# MCU.net
KiCad netlist of a schematic drawn in Altium Designer
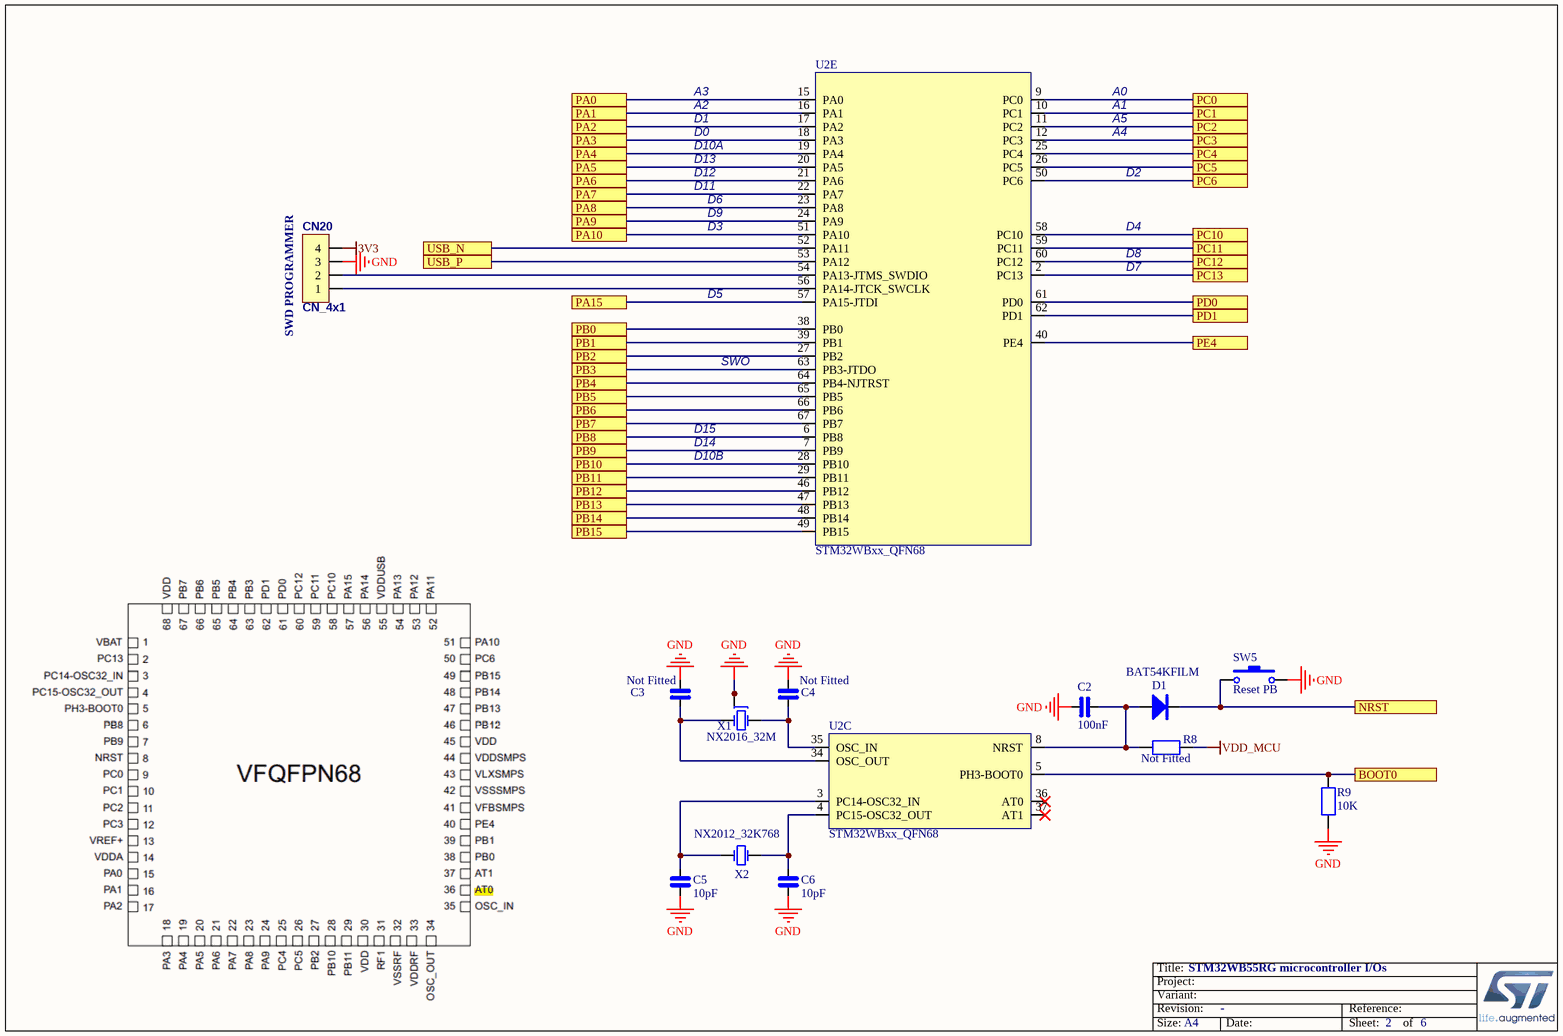
[diagram p0: MCU.SchDoc]

(export (version "E")
  (design (tool "Eeschema 10.0.6"))
  (components
    (comp (ref "C2")
      (value "100nF")
      (footprint "0603_CAP_NPOL")
      (description "Capacitor_not polarized")
      (libsource (lib "ST_Lib3D") (part "CAP_NPOL"))
    )
    (comp (ref "C3")
      (value "TBD")
      (footprint "0603_CAP_NPOL")
      (description "Capacitor_not polarized")
      (fields (field (name "FITTED") "Not Fitted"))
      (libsource (lib "ST_Lib3D") (part "CAP_NPOL"))
    )
    (comp (ref "C4")
      (value "TBD")
      (footprint "0603_CAP_NPOL")
      (description "Capacitor_not polarized")
      (fields (field (name "FITTED") "Not Fitted"))
      (libsource (lib "ST_Lib3D") (part "CAP_NPOL"))
    )
    (comp (ref "C5")
      (value "10pF")
      (footprint "0603_CAP_NPOL")
      (description "Capacitor_not polarized")
      (libsource (lib "ST_Lib3D") (part "CAP_NPOL"))
    )
    (comp (ref "C6")
      (value "10pF")
      (footprint "0603_CAP_NPOL")
      (description "Capacitor_not polarized")
      (libsource (lib "ST_Lib3D") (part "CAP_NPOL"))
    )
    (comp (ref "CN20") (value "CN_4x1") (footprint "GP_4x1") (libsource (lib "goldpin_male") (part "CN_4x1")))
    (comp (ref "D1")
      (value "BAT54KFILM")
      (footprint "SOD523")
      (description "Schottky Diode")
      (libsource (lib "Lib3D_Altium10_Schlib") (part "BAT54K"))
    )
    (comp (ref "R8")
      (value "100K (not fitted)")
      (footprint "0402_RES")
      (description "Resistor")
      (fields (field (name "FITTED") "Not Fitted"))
      (libsource (lib "Lib3D_Altium10_Schlib") (part "RES"))
    )
    (comp (ref "R9")
      (value "10K")
      (footprint "0402_RES")
      (description "Resistor")
      (libsource (lib "Lib3D_Altium10_Schlib") (part "RES"))
    )
    (comp (ref "SW5")
      (value "Reset PB")
      (footprint "SW-PB SMD KMR2")
      (description "Push-button SMD")
      (libsource (lib "ST_Lib3D") (part "SW-PB_1"))
    )
    (comp (ref "U2")
      (value "STM32WBxx_QFN68")
      (footprint "VFQFPN68_8x8x0.1_p0.4")
      (libsource (lib "Active") (part "STM32WBxx_QFN68"))
    )
    (comp (ref "X1")
      (value "NX2016_32M")
      (footprint "NX2016_4P")
      (description "Crystal NDK 2.0x1.6mm  32 MHz")
      (fields (field (name "MANUFACTURER") "NDK"))
      (libsource (lib "Xtal") (part "NX2016_32M"))
    )
    (comp (ref "X2")
      (value "NX2012_32K768")
      (footprint "NX2012_2P")
      (description "Crystal NDK 2.0x1.2mm  32.768 KHz")
      (fields (field (name "MANUFACTURER") "NDK"))
      (libsource (lib "Xtal") (part "NX2012_32K768"))
    )
  )
  (nets
    (net (code "1") (name "/BOOT0") (class "Default")
      (node (ref "R9") (pin "1") (pinfunction "1_1") (pintype "passive"))
      (node (ref "U2") (pin "5") (pinfunction "PH3-BOOT0_5") (pintype "passive"))
    )
    (net (code "2") (name "/NRST") (class "Default")
      (node (ref "D1") (pin "K") (pinfunction "K_K") (pintype "passive"))
      (node (ref "SW5") (pin "1") (pinfunction "1_1") (pintype "passive"))
    )
    (net (code "3") (name "/PA0") (class "Default")
      (node (ref "U2") (pin "15") (pinfunction "PA0_15") (pintype "passive"))
    )
    (net (code "4") (name "/PA1") (class "Default")
      (node (ref "U2") (pin "16") (pinfunction "PA1_16") (pintype "passive"))
    )
    (net (code "5") (name "/PA2") (class "Default")
      (node (ref "U2") (pin "17") (pinfunction "PA2_17") (pintype "passive"))
    )
    (net (code "6") (name "/PA3") (class "Default")
      (node (ref "U2") (pin "18") (pinfunction "PA3_18") (pintype "passive"))
    )
    (net (code "7") (name "/PA4") (class "Default")
      (node (ref "U2") (pin "19") (pinfunction "PA4_19") (pintype "passive"))
    )
    (net (code "8") (name "/PA5") (class "Default")
      (node (ref "U2") (pin "20") (pinfunction "PA5_20") (pintype "passive"))
    )
    (net (code "9") (name "/PA6") (class "Default")
      (node (ref "U2") (pin "21") (pinfunction "PA6_21") (pintype "passive"))
    )
    (net (code "10") (name "/PA7") (class "Default")
      (node (ref "U2") (pin "22") (pinfunction "PA7_22") (pintype "passive"))
    )
    (net (code "11") (name "/PA8") (class "Default")
      (node (ref "U2") (pin "23") (pinfunction "PA8_23") (pintype "passive"))
    )
    (net (code "12") (name "/PA9") (class "Default")
      (node (ref "U2") (pin "24") (pinfunction "PA9_24") (pintype "passive"))
    )
    (net (code "13") (name "/PA10") (class "Default")
      (node (ref "U2") (pin "51") (pinfunction "PA10_51") (pintype "passive"))
    )
    (net (code "14") (name "/PA15") (class "Default")
      (node (ref "U2") (pin "57") (pinfunction "PA15-JTDI_57") (pintype "passive"))
    )
    (net (code "15") (name "/PB0") (class "Default")
      (node (ref "U2") (pin "38") (pinfunction "PB0_38") (pintype "passive"))
    )
    (net (code "16") (name "/PB1") (class "Default")
      (node (ref "U2") (pin "39") (pinfunction "PB1_39") (pintype "passive"))
    )
    (net (code "17") (name "/PB2") (class "Default")
      (node (ref "U2") (pin "27") (pinfunction "PB2_27") (pintype "passive"))
    )
    (net (code "18") (name "/PB3") (class "Default")
      (node (ref "U2") (pin "63") (pinfunction "PB3-JTDO_63") (pintype "passive"))
    )
    (net (code "19") (name "/PB4") (class "Default")
      (node (ref "U2") (pin "64") (pinfunction "PB4-NJTRST_64") (pintype "passive"))
    )
    (net (code "20") (name "/PB5") (class "Default")
      (node (ref "U2") (pin "65") (pinfunction "PB5_65") (pintype "passive"))
    )
    (net (code "21") (name "/PB6") (class "Default")
      (node (ref "U2") (pin "66") (pinfunction "PB6_66") (pintype "passive"))
    )
    (net (code "22") (name "/PB7") (class "Default")
      (node (ref "U2") (pin "67") (pinfunction "PB7_67") (pintype "passive"))
    )
    (net (code "23") (name "/PB8") (class "Default")
      (node (ref "U2") (pin "6") (pinfunction "PB8_6") (pintype "passive"))
    )
    (net (code "24") (name "/PB9") (class "Default")
      (node (ref "U2") (pin "7") (pinfunction "PB9_7") (pintype "passive"))
    )
    (net (code "25") (name "/PB10") (class "Default")
      (node (ref "U2") (pin "28") (pinfunction "PB10_28") (pintype "passive"))
    )
    (net (code "26") (name "/PB11") (class "Default")
      (node (ref "U2") (pin "29") (pinfunction "PB11_29") (pintype "passive"))
    )
    (net (code "27") (name "/PB12") (class "Default")
      (node (ref "U2") (pin "46") (pinfunction "PB12_46") (pintype "passive"))
    )
    (net (code "28") (name "/PB13") (class "Default")
      (node (ref "U2") (pin "47") (pinfunction "PB13_47") (pintype "passive"))
    )
    (net (code "29") (name "/PB14") (class "Default")
      (node (ref "U2") (pin "48") (pinfunction "PB14_48") (pintype "passive"))
    )
    (net (code "30") (name "/PB15") (class "Default")
      (node (ref "U2") (pin "49") (pinfunction "PB15_49") (pintype "passive"))
    )
    (net (code "31") (name "/PC0") (class "Default")
      (node (ref "U2") (pin "9") (pinfunction "PC0_9") (pintype "passive"))
    )
    (net (code "32") (name "/PC1") (class "Default")
      (node (ref "U2") (pin "10") (pinfunction "PC1_10") (pintype "passive"))
    )
    (net (code "33") (name "/PC2") (class "Default")
      (node (ref "U2") (pin "11") (pinfunction "PC2_11") (pintype "passive"))
    )
    (net (code "34") (name "/PC3") (class "Default")
      (node (ref "U2") (pin "12") (pinfunction "PC3_12") (pintype "passive"))
    )
    (net (code "35") (name "/PC4") (class "Default")
      (node (ref "U2") (pin "25") (pinfunction "PC4_25") (pintype "passive"))
    )
    (net (code "36") (name "/PC5") (class "Default")
      (node (ref "U2") (pin "26") (pinfunction "PC5_26") (pintype "passive"))
    )
    (net (code "37") (name "/PC6") (class "Default")
      (node (ref "U2") (pin "50") (pinfunction "PC6_50") (pintype "passive"))
    )
    (net (code "38") (name "/PC10") (class "Default")
      (node (ref "U2") (pin "58") (pinfunction "PC10_58") (pintype "passive"))
    )
    (net (code "39") (name "/PC11") (class "Default")
      (node (ref "U2") (pin "59") (pinfunction "PC11_59") (pintype "passive"))
    )
    (net (code "40") (name "/PC12") (class "Default")
      (node (ref "U2") (pin "60") (pinfunction "PC12_60") (pintype "passive"))
    )
    (net (code "41") (name "/PC13") (class "Default")
      (node (ref "U2") (pin "2") (pinfunction "PC13_2") (pintype "passive"))
    )
    (net (code "42") (name "/PD0") (class "Default")
      (node (ref "U2") (pin "61") (pinfunction "PD0_61") (pintype "passive"))
    )
    (net (code "43") (name "/PD1") (class "Default")
      (node (ref "U2") (pin "62") (pinfunction "PD1_62") (pintype "passive"))
    )
    (net (code "44") (name "/PE4") (class "Default")
      (node (ref "U2") (pin "40") (pinfunction "PE4_40") (pintype "passive"))
    )
    (net (code "45") (name "/USB_N") (class "Default")
      (node (ref "U2") (pin "52") (pinfunction "PA11_52") (pintype "passive"))
    )
    (net (code "46") (name "/USB_P") (class "Default")
      (node (ref "U2") (pin "53") (pinfunction "PA12_53") (pintype "passive"))
    )
    (net (code "47") (name "3V3") (class "Default")
      (node (ref "CN20") (pin "4") (pinfunction "4_4") (pintype "passive"))
    )
    (net (code "48") (name "GND") (class "Default")
      (node (ref "C2") (pin "1") (pinfunction "1_1") (pintype "passive"))
      (node (ref "C3") (pin "2") (pinfunction "2_2") (pintype "passive"))
      (node (ref "C4") (pin "2") (pinfunction "2_2") (pintype "passive"))
      (node (ref "C5") (pin "2") (pinfunction "2_2") (pintype "passive"))
      (node (ref "C6") (pin "2") (pinfunction "2_2") (pintype "passive"))
      (node (ref "CN20") (pin "3") (pinfunction "3_3") (pintype "passive"))
      (node (ref "R9") (pin "2") (pinfunction "2_2") (pintype "passive"))
      (node (ref "SW5") (pin "2") (pinfunction "2_2") (pintype "passive"))
      (node (ref "X1") (pin "2") (pinfunction "2_2") (pintype "passive"))
      (node (ref "X1") (pin "4") (pinfunction "4_4") (pintype "passive"))
    )
    (net (code "49") (name "Net-(U2C-NRST)") (class "Default")
      (node (ref "C2") (pin "2") (pinfunction "2_2") (pintype "passive"))
      (node (ref "D1") (pin "A") (pinfunction "A_A") (pintype "passive"))
      (node (ref "R8") (pin "2") (pinfunction "2_2") (pintype "passive"))
      (node (ref "U2") (pin "8") (pinfunction "NRST_8") (pintype "passive"))
    )
    (net (code "50") (name "Net-(U2C-OSC_IN)") (class "Default")
      (node (ref "C4") (pin "1") (pinfunction "1_1") (pintype "passive"))
      (node (ref "U2") (pin "35") (pinfunction "OSC_IN_35") (pintype "passive"))
      (node (ref "X1") (pin "1") (pinfunction "OSC1_1") (pintype "passive"))
    )
    (net (code "51") (name "Net-(U2C-OSC_OUT)") (class "Default")
      (node (ref "C3") (pin "1") (pinfunction "1_1") (pintype "passive"))
      (node (ref "U2") (pin "34") (pinfunction "OSC_OUT_34") (pintype "passive"))
      (node (ref "X1") (pin "3") (pinfunction "OSC2_3") (pintype "passive"))
    )
    (net (code "52") (name "Net-(U2C-PC14-OSC32_IN)") (class "Default")
      (node (ref "C5") (pin "1") (pinfunction "1_1") (pintype "passive"))
      (node (ref "U2") (pin "3") (pinfunction "PC14-OSC32_IN_3") (pintype "passive"))
      (node (ref "X2") (pin "1") (pinfunction "OSC1_1") (pintype "passive"))
    )
    (net (code "53") (name "Net-(U2C-PC15-OSC32_OUT)") (class "Default")
      (node (ref "C6") (pin "1") (pinfunction "1_1") (pintype "passive"))
      (node (ref "U2") (pin "4") (pinfunction "PC15-OSC32_OUT_4") (pintype "passive"))
      (node (ref "X2") (pin "2") (pinfunction "OSC2_2") (pintype "passive"))
    )
    (net (code "54") (name "Net-(U2E-PA13-JTMS_SWDIO)") (class "Default")
      (node (ref "CN20") (pin "2") (pinfunction "2_2") (pintype "passive"))
      (node (ref "U2") (pin "54") (pinfunction "PA13-JTMS_SWDIO_54") (pintype "passive"))
    )
    (net (code "55") (name "Net-(U2E-PA14-JTCK_SWCLK)") (class "Default")
      (node (ref "CN20") (pin "1") (pinfunction "1_1") (pintype "passive"))
      (node (ref "U2") (pin "56") (pinfunction "PA14-JTCK_SWCLK_56") (pintype "passive"))
    )
    (net (code "56") (name "VDD_MCU") (class "Default")
      (node (ref "R8") (pin "1") (pinfunction "1_1") (pintype "passive"))
    )
    (net (code "57") (name "unconnected-(U2C-AT0-Pad36)") (class "Default")
      (node (ref "U2") (pin "36") (pinfunction "AT0_36") (pintype "passive+no_connect"))
    )
    (net (code "58") (name "unconnected-(U2C-AT1-Pad37)") (class "Default")
      (node (ref "U2") (pin "37") (pinfunction "AT1_37") (pintype "passive+no_connect"))
    )
  )
)
